# mmmmm.net
KiCad netlist of a schematic drawn in Altium Designer
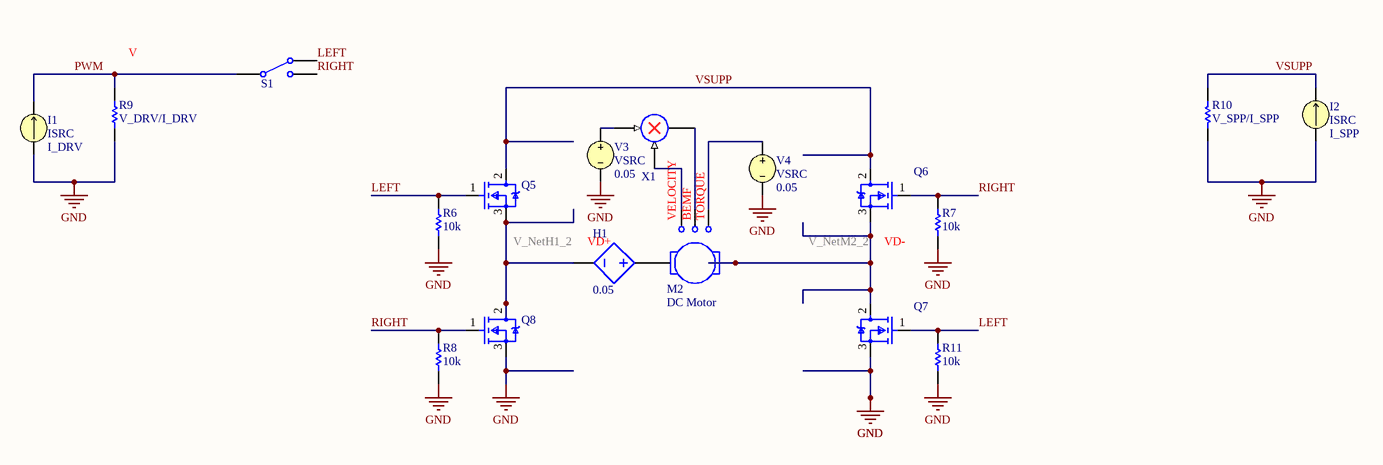
[diagram p0: mmmmm.SchDoc]

(export (version "E")
  (design (tool "Eeschema 10.0.6"))
  (components
    (comp (ref "H1")
      (value "Current Controlled Voltage Source")
      (fields (field (name "GAIN") "0.05"))
      (libsource (lib "Simulation Generic Components") (part "CCVS"))
    )
    (comp (ref "I1")
      (value "ISRC")
      (description "Current Source")
      (fields (field (name "DC MAGNITUDE") "I_DRV") (field (name "PUBLISHER") "Altium Limited"))
      (libsource (lib "Simulation Generic Components") (part "ISRC"))
    )
    (comp (ref "I2")
      (value "ISRC")
      (description "Current Source")
      (fields (field (name "ALTIUM_VALUE") "I_SPP") (field (name "PUBLISHER") "Altium Limited"))
      (libsource (lib "Simulation Generic Components") (part "ISRC"))
    )
    (comp (ref "M2") (value "DC Motor") (libsource (lib "Simulation Generic Components") (part "DC Motor")))
    (comp (ref "Q5")
      (value "Trans_Infineon_IRF540NPBF_eec")
      (footprint "Infineon_IRF540NPBF_0")
      (description "TRANS MOSFET N-CH 100V 33A TO-220AB")
      (fields (field (name "PART NUMBER") "IRF540NPBF") (field (name "MANUFACTURER") "Infineon"))
      (libsource (lib "Trans_Infineon_IRF540NPBF_eec") (part "Trans_Infineon_IRF540NPBF_eec"))
    )
    (comp (ref "Q6")
      (value "Trans_Infineon_IRF540NPBF_eec")
      (footprint "Infineon_IRF540NPBF_0")
      (description "TRANS MOSFET N-CH 100V 33A TO-220AB")
      (fields (field (name "PART NUMBER") "IRF540NPBF") (field (name "MANUFACTURER") "Infineon"))
      (libsource (lib "Trans_Infineon_IRF540NPBF_eec") (part "Trans_Infineon_IRF540NPBF_eec"))
    )
    (comp (ref "Q7")
      (value "Trans_Infineon_IRF540NPBF_eec")
      (footprint "Infineon_IRF540NPBF_0")
      (description "TRANS MOSFET N-CH 100V 33A TO-220AB")
      (fields (field (name "PART NUMBER") "IRF540NPBF") (field (name "MANUFACTURER") "Infineon"))
      (libsource (lib "Trans_Infineon_IRF540NPBF_eec") (part "Trans_Infineon_IRF540NPBF_eec"))
    )
    (comp (ref "Q8")
      (value "Trans_Infineon_IRF540NPBF_eec")
      (footprint "Infineon_IRF540NPBF_0")
      (description "TRANS MOSFET N-CH 100V 33A TO-220AB")
      (fields (field (name "PART NUMBER") "IRF540NPBF") (field (name "MANUFACTURER") "Infineon"))
      (libsource (lib "Trans_Infineon_IRF540NPBF_eec") (part "Trans_Infineon_IRF540NPBF_eec"))
    )
    (comp (ref "R6")
      (value "10k")
      (description "Resistor")
      (libsource (lib "Simulation Generic Components") (part "Resistor"))
    )
    (comp (ref "R7")
      (value "10k")
      (description "Resistor")
      (libsource (lib "Simulation Generic Components") (part "Resistor"))
    )
    (comp (ref "R8")
      (value "10k")
      (description "Resistor")
      (libsource (lib "Simulation Generic Components") (part "Resistor"))
    )
    (comp (ref "R9")
      (value "V_DRV/I_DRV")
      (description "Resistor")
      (libsource (lib "Simulation Generic Components") (part "Resistor"))
    )
    (comp (ref "R10")
      (value "V_SPP/I_SPP")
      (description "Resistor")
      (libsource (lib "Simulation Generic Components") (part "Resistor"))
    )
    (comp (ref "R11")
      (value "10k")
      (description "Resistor")
      (libsource (lib "Simulation Generic Components") (part "Resistor"))
    )
    (comp (ref "S1")
      (value "Single-Pole, Double-Throw Switch")
      (libsource (lib "Simulation Generic Components") (part "SPDT SW"))
    )
    (comp (ref "V3")
      (value "VSRC")
      (description "Voltage Source")
      (fields (field (name "ALTIUM_VALUE") "0.05") (field (name "PUBLISHER") "Altium Limited"))
      (libsource (lib "Simulation Generic Components") (part "VSRC"))
    )
    (comp (ref "V4")
      (value "VSRC")
      (description "Voltage Source")
      (fields (field (name "ALTIUM_VALUE") "0.05") (field (name "PUBLISHER") "Altium Limited"))
      (libsource (lib "Simulation Generic Components") (part "VSRC"))
    )
    (comp (ref "X1")
      (value "Voltage Multiplier")
      (libsource (lib "Simulation Generic Components") (part "Voltage Multiplier"))
    )
  )
  (nets
    (net (code "2") (name "/LEFT") (class "Default")
      (node (ref "Q5") (pin "1") (pinfunction "GATE_1") (pintype "passive"))
      (node (ref "Q7") (pin "1") (pinfunction "GATE_1") (pintype "passive"))
      (node (ref "R11") (pin "2") (pinfunction "2_2") (pintype "passive"))
      (node (ref "R6") (pin "2") (pinfunction "2_2") (pintype "passive"))
      (node (ref "S1") (pin "3") (pinfunction "3_3") (pintype "passive"))
    )
    (net (code "3") (name "/PWM") (class "Default")
      (node (ref "I1") (pin "2") (pinfunction "2_2") (pintype "passive"))
      (node (ref "R9") (pin "2") (pinfunction "2_2") (pintype "passive"))
      (node (ref "S1") (pin "1") (pinfunction "1_1") (pintype "passive"))
    )
    (net (code "4") (name "/RIGHT") (class "Default")
      (node (ref "Q6") (pin "1") (pinfunction "GATE_1") (pintype "passive"))
      (node (ref "Q8") (pin "1") (pinfunction "GATE_1") (pintype "passive"))
      (node (ref "R7") (pin "2") (pinfunction "2_2") (pintype "passive"))
      (node (ref "R8") (pin "2") (pinfunction "2_2") (pintype "passive"))
      (node (ref "S1") (pin "2") (pinfunction "2_2") (pintype "passive"))
    )
    (net (code "5") (name "/VSUPP") (class "Default")
      (node (ref "I2") (pin "2") (pinfunction "2_2") (pintype "passive"))
      (node (ref "Q5") (pin "2") (pinfunction "DRAIN_2") (pintype "passive"))
      (node (ref "Q6") (pin "2") (pinfunction "DRAIN_2") (pintype "passive"))
      (node (ref "R10") (pin "2") (pinfunction "2_2") (pintype "passive"))
    )
    (net (code "6") (name "GND") (class "Default")
      (node (ref "I1") (pin "1") (pinfunction "1_1") (pintype "passive"))
      (node (ref "I2") (pin "1") (pinfunction "1_1") (pintype "passive"))
      (node (ref "Q7") (pin "3") (pinfunction "SOURCE_3") (pintype "passive"))
      (node (ref "Q8") (pin "3") (pinfunction "SOURCE_3") (pintype "passive"))
      (node (ref "R10") (pin "1") (pinfunction "1_1") (pintype "passive"))
      (node (ref "R11") (pin "1") (pinfunction "1_1") (pintype "passive"))
      (node (ref "R6") (pin "1") (pinfunction "1_1") (pintype "passive"))
      (node (ref "R7") (pin "1") (pinfunction "1_1") (pintype "passive"))
      (node (ref "R8") (pin "1") (pinfunction "1_1") (pintype "passive"))
      (node (ref "R9") (pin "1") (pinfunction "1_1") (pintype "passive"))
      (node (ref "V3") (pin "2") (pinfunction "2_2") (pintype "passive"))
      (node (ref "V4") (pin "2") (pinfunction "2_2") (pintype "passive"))
    )
    (net (code "7") (name "Net-(H1-Pad1)") (class "Default")
      (node (ref "H1") (pin "1") (pinfunction "1_1") (pintype "passive"))
      (node (ref "M2") (pin "1") (pinfunction "1_1") (pintype "passive"))
    )
    (net (code "8") (name "Net-(M2-Pad3)") (class "Default")
      (node (ref "M2") (pin "3") (pinfunction "3_3") (pintype "passive"))
      (node (ref "X1") (pin "2") (pinfunction "2_2") (pintype "input"))
    )
    (net (code "9") (name "Net-(M2-Pad4)") (class "Default")
      (node (ref "M2") (pin "4") (pinfunction "4_4") (pintype "passive"))
      (node (ref "X1") (pin "3") (pinfunction "3_3") (pintype "passive"))
    )
    (net (code "10") (name "Net-(M2-Pad5)") (class "Default")
      (node (ref "M2") (pin "5") (pinfunction "5_5") (pintype "passive"))
      (node (ref "V4") (pin "1") (pinfunction "1_1") (pintype "passive"))
    )
    (net (code "11") (name "Net-(Q5-SOURCE)") (class "Default")
      (node (ref "H1") (pin "2") (pinfunction "2_2") (pintype "passive"))
      (node (ref "Q5") (pin "3") (pinfunction "SOURCE_3") (pintype "passive"))
      (node (ref "Q8") (pin "2") (pinfunction "DRAIN_2") (pintype "passive"))
    )
    (net (code "12") (name "Net-(Q6-SOURCE)") (class "Default")
      (node (ref "M2") (pin "2") (pinfunction "2_2") (pintype "passive"))
      (node (ref "Q6") (pin "3") (pinfunction "SOURCE_3") (pintype "passive"))
      (node (ref "Q7") (pin "2") (pinfunction "DRAIN_2") (pintype "passive"))
    )
    (net (code "13") (name "Net-(V3-Pad1)") (class "Default")
      (node (ref "V3") (pin "1") (pinfunction "1_1") (pintype "passive"))
      (node (ref "X1") (pin "1") (pinfunction "1_1") (pintype "input"))
    )
  )
)
